# Accel.net
KiCad netlist of a schematic drawn in Altium Designer
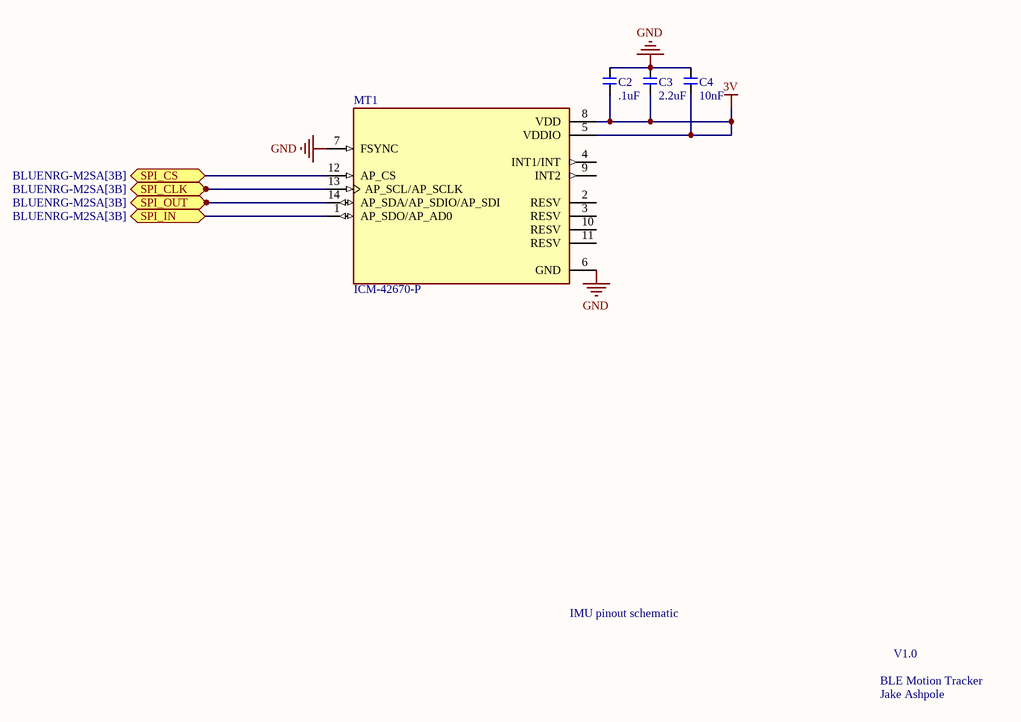
[diagram p0: Accel.SchDoc]

(export (version "E")
  (design (tool "Eeschema 10.0.6"))
  (components
    (comp (ref "C2")
      (value ".1uF")
      (footprint "CAP-0603")
      (fields (field (name "SOURCE") "ife19_Elec_Library.SchLib"))
      (libsource (lib "Illini Formula Electric") (part "CAP-0603"))
    )
    (comp (ref "C3")
      (value "2.2uF")
      (footprint "CAP-0603")
      (fields (field (name "SOURCE") "ife19_Elec_Library.SchLib"))
      (libsource (lib "Illini Formula Electric") (part "CAP-0603"))
    )
    (comp (ref "C4")
      (value "10nF")
      (footprint "CAP-0603")
      (fields (field (name "SOURCE") "ife19_Elec_Library.SchLib"))
      (libsource (lib "Illini Formula Electric") (part "CAP-0603"))
    )
    (comp (ref "MT1")
      (value "ICM-42670-P")
      (footprint "XDCR_ICM-42670-P")
      (description "https://www.mouser.com/ProductDetail/TDK-InvenSense/ICM-42670-P?qs=iLbezkQI%2BsgK8sMF5V7fQQ%3D%3D")
      (libsource (lib "ICM-42670-P") (part "ICM-42670-P"))
    )
  )
  (nets
    (net (code "1") (name "/SPI_CLK") (class "Default")
      (node (ref "MT1") (pin "13") (pinfunction "AP_SCL/AP_SCLK_13") (pintype "input"))
    )
    (net (code "2") (name "/SPI_CS") (class "Default")
      (node (ref "MT1") (pin "12") (pinfunction "AP_CS_12") (pintype "input"))
    )
    (net (code "3") (name "/SPI_IN") (class "Default")
      (node (ref "MT1") (pin "1") (pinfunction "AP_SDO/AP_AD0_1") (pintype "bidirectional"))
    )
    (net (code "4") (name "/SPI_OUT") (class "Default")
      (node (ref "MT1") (pin "14") (pinfunction "AP_SDA/AP_SDIO/AP_SDI_14") (pintype "bidirectional"))
    )
    (net (code "5") (name "3V") (class "Default")
      (node (ref "C2") (pin "1") (pinfunction "1_1") (pintype "passive"))
      (node (ref "C3") (pin "1") (pinfunction "1_1") (pintype "passive"))
      (node (ref "C4") (pin "1") (pinfunction "1_1") (pintype "passive"))
      (node (ref "MT1") (pin "5") (pinfunction "VDDIO_5") (pintype "power_in"))
      (node (ref "MT1") (pin "8") (pinfunction "VDD_8") (pintype "power_in"))
    )
    (net (code "6") (name "GND") (class "Default")
      (node (ref "C2") (pin "2") (pinfunction "2_2") (pintype "passive"))
      (node (ref "C3") (pin "2") (pinfunction "2_2") (pintype "passive"))
      (node (ref "C4") (pin "2") (pinfunction "2_2") (pintype "passive"))
      (node (ref "MT1") (pin "6") (pinfunction "GND_6") (pintype "power_in"))
      (node (ref "MT1") (pin "7") (pinfunction "FSYNC_7") (pintype "input"))
    )
    (net (code "7") (name "unconnected-(MT1-INT1{slash}INT-Pad4)") (class "Default")
      (node (ref "MT1") (pin "4") (pinfunction "INT1/INT_4") (pintype "output"))
    )
    (net (code "8") (name "unconnected-(MT1-INT2-Pad9)") (class "Default")
      (node (ref "MT1") (pin "9") (pinfunction "INT2_9") (pintype "output"))
    )
    (net (code "9") (name "unconnected-(MT1-RESV-Pad2)") (class "Default")
      (node (ref "MT1") (pin "2") (pinfunction "RESV_2") (pintype "passive"))
    )
    (net (code "10") (name "unconnected-(MT1-RESV-Pad3)") (class "Default")
      (node (ref "MT1") (pin "3") (pinfunction "RESV_3") (pintype "passive"))
    )
    (net (code "11") (name "unconnected-(MT1-RESV-Pad10)") (class "Default")
      (node (ref "MT1") (pin "10") (pinfunction "RESV_10") (pintype "passive"))
    )
    (net (code "12") (name "unconnected-(MT1-RESV-Pad11)") (class "Default")
      (node (ref "MT1") (pin "11") (pinfunction "RESV_11") (pintype "passive"))
    )
  )
)
